# Flow_sensors.net
KiCad netlist of a schematic drawn in Altium Designer
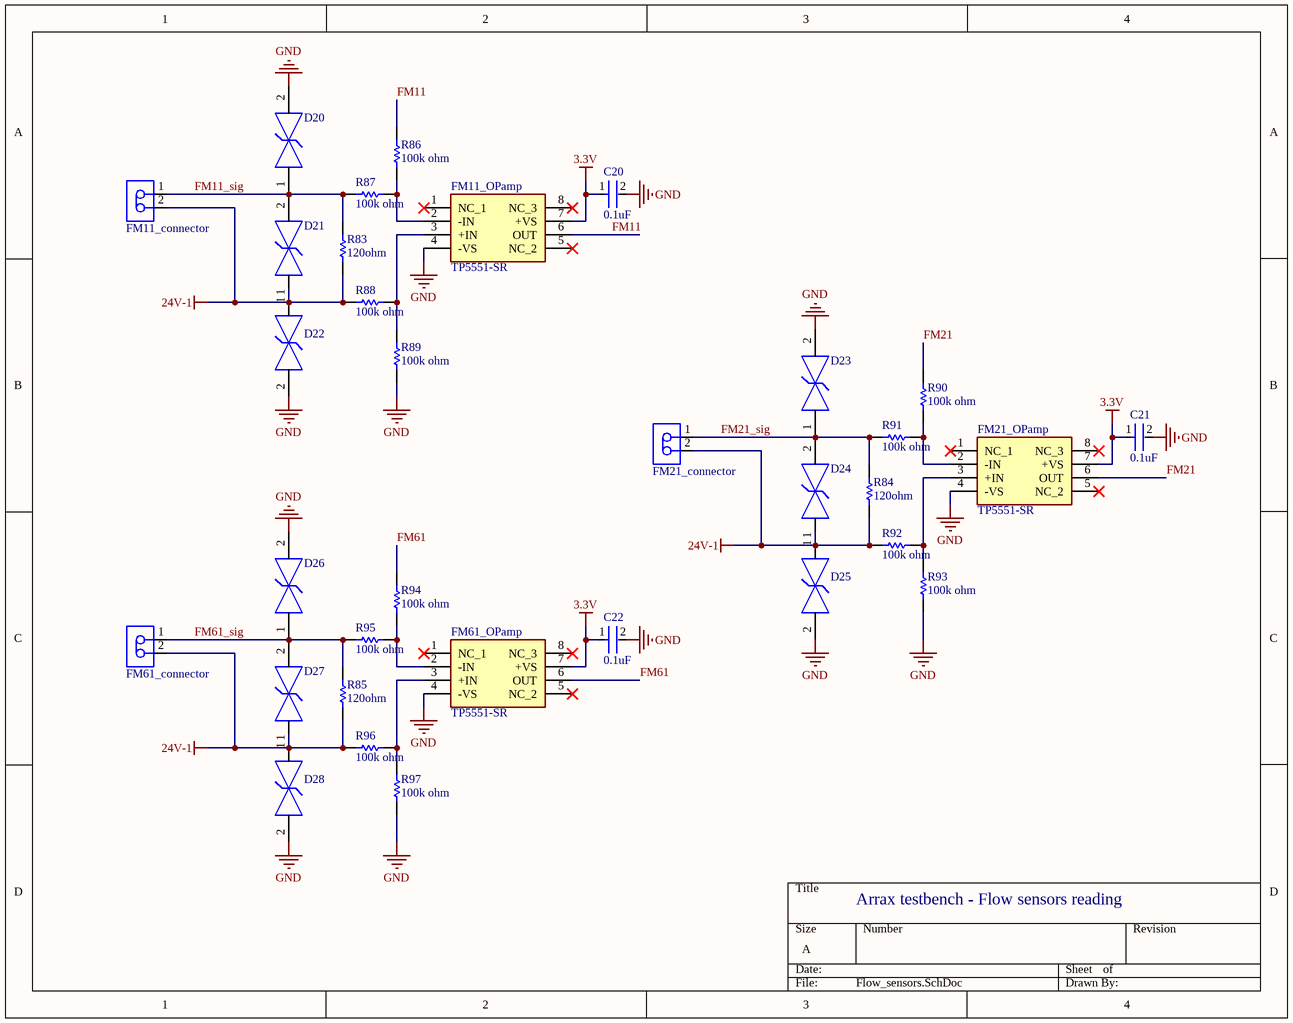
[diagram p0: Flow_sensors.SchDoc]

(export (version "E")
  (design (tool "Eeschema 10.0.6"))
  (components
    (comp (ref "C20")
      (value "0.1uF")
      (footprint "FP-CC0805-0_85-MFG")
      (description "CAP CER 0.1UF 50V X7R 0805")
      (fields (field (name "TOLERANCE") "0.1") (field (name "MANUFACTURER PART NUMBER") "CC0805KRX7R9BB104"))
      (libsource (lib "Altium Content Vault") (part "11868f565c42a9108669ba33697ecf6"))
    )
    (comp (ref "C21")
      (value "0.1uF")
      (footprint "FP-CC0805-0_85-MFG")
      (description "CAP CER 0.1UF 50V X7R 0805")
      (fields (field (name "TOLERANCE") "0.1") (field (name "MANUFACTURER PART NUMBER") "CC0805KRX7R9BB104"))
      (libsource (lib "Altium Content Vault") (part "11868f565c42a9108669ba33697ecf6"))
    )
    (comp (ref "C22")
      (value "0.1uF")
      (footprint "FP-CC0805-0_85-MFG")
      (description "CAP CER 0.1UF 50V X7R 0805")
      (fields (field (name "TOLERANCE") "0.1") (field (name "MANUFACTURER PART NUMBER") "CC0805KRX7R9BB104"))
      (libsource (lib "Altium Content Vault") (part "11868f565c42a9108669ba33697ecf6"))
    )
    (comp (ref "D20")
      (value "SMBJ33CA-13-F")
      (footprint "FP-SMB-CA-MFG")
      (description "TVS DIODE 33V 53.3V SMB")
      (libsource (lib "Altium Content Vault") (part "876f4347bf90aa6f500f43e3cd03972"))
    )
    (comp (ref "D21")
      (value "SMBJ33CA-13-F")
      (footprint "FP-SMB-CA-MFG")
      (description "TVS DIODE 33V 53.3V SMB")
      (libsource (lib "Altium Content Vault") (part "876f4347bf90aa6f500f43e3cd03972"))
    )
    (comp (ref "D22")
      (value "SMBJ33CA-13-F")
      (footprint "FP-SMB-CA-MFG")
      (description "TVS DIODE 33V 53.3V SMB")
      (libsource (lib "Altium Content Vault") (part "876f4347bf90aa6f500f43e3cd03972"))
    )
    (comp (ref "D23")
      (value "SMBJ33CA-13-F")
      (footprint "FP-SMB-CA-MFG")
      (description "TVS DIODE 33V 53.3V SMB")
      (libsource (lib "Altium Content Vault") (part "876f4347bf90aa6f500f43e3cd03972"))
    )
    (comp (ref "D24")
      (value "SMBJ33CA-13-F")
      (footprint "FP-SMB-CA-MFG")
      (description "TVS DIODE 33V 53.3V SMB")
      (libsource (lib "Altium Content Vault") (part "876f4347bf90aa6f500f43e3cd03972"))
    )
    (comp (ref "D25")
      (value "SMBJ33CA-13-F")
      (footprint "FP-SMB-CA-MFG")
      (description "TVS DIODE 33V 53.3V SMB")
      (libsource (lib "Altium Content Vault") (part "876f4347bf90aa6f500f43e3cd03972"))
    )
    (comp (ref "D26")
      (value "SMBJ33CA-13-F")
      (footprint "FP-SMB-CA-MFG")
      (description "TVS DIODE 33V 53.3V SMB")
      (libsource (lib "Altium Content Vault") (part "876f4347bf90aa6f500f43e3cd03972"))
    )
    (comp (ref "D27")
      (value "SMBJ33CA-13-F")
      (footprint "FP-SMB-CA-MFG")
      (description "TVS DIODE 33V 53.3V SMB")
      (libsource (lib "Altium Content Vault") (part "876f4347bf90aa6f500f43e3cd03972"))
    )
    (comp (ref "D28")
      (value "SMBJ33CA-13-F")
      (footprint "FP-SMB-CA-MFG")
      (description "TVS DIODE 33V 53.3V SMB")
      (libsource (lib "Altium Content Vault") (part "876f4347bf90aa6f500f43e3cd03972"))
    )
    (comp (ref "FM11_connector")
      (value "640456-2")
      (footprint "TECO-640456-2_V")
      (fields (field (name "MANUFACTURER") "TE Connectivity"))
      (libsource (lib "Altium Content Vault") (part "CN-2P-F-QF2"))
    )
    (comp (ref "FM11_OPamp")
      (value "TP5551-SR")
      (footprint "SamacSys:SOIC127P600X175-8N")
      (description "Integrated Circuit")
      (libsource (lib "*") (part "TP5551-SR"))
    )
    (comp (ref "FM21_connector")
      (value "640456-2")
      (footprint "TECO-640456-2_V")
      (fields (field (name "MANUFACTURER") "TE Connectivity"))
      (libsource (lib "Altium Content Vault") (part "CN-2P-F-QF2"))
    )
    (comp (ref "FM21_OPamp")
      (value "TP5551-SR")
      (footprint "SamacSys:SOIC127P600X175-8N")
      (description "Integrated Circuit")
      (libsource (lib "*") (part "TP5551-SR"))
    )
    (comp (ref "FM61_connector")
      (value "640456-2")
      (footprint "TECO-640456-2_V")
      (fields (field (name "MANUFACTURER") "TE Connectivity"))
      (libsource (lib "Altium Content Vault") (part "CN-2P-F-QF2"))
    )
    (comp (ref "FM61_OPamp")
      (value "TP5551-SR")
      (footprint "SamacSys:SOIC127P600X175-8N")
      (description "Integrated Circuit")
      (libsource (lib "*") (part "TP5551-SR"))
    )
    (comp (ref "R83")
      (value "120ohm")
      (footprint "RESC2013X60X40ML20T25")
      (fields (field (name "MANUFACTURER") "Panasonic") (field (name "PART NUMBER") "ERA6AEB121V"))
      (libsource (lib "Altium Content Vault") (part "RES"))
    )
    (comp (ref "R84")
      (value "120ohm")
      (footprint "RESC2013X60X40ML20T25")
      (fields (field (name "MANUFACTURER") "Panasonic") (field (name "PART NUMBER") "ERA6AEB121V"))
      (libsource (lib "Altium Content Vault") (part "RES"))
    )
    (comp (ref "R85")
      (value "120ohm")
      (footprint "RESC2013X60X40ML20T25")
      (fields (field (name "MANUFACTURER") "Panasonic") (field (name "PART NUMBER") "ERA6AEB121V"))
      (libsource (lib "Altium Content Vault") (part "RES"))
    )
    (comp (ref "R86")
      (value "100k ohm")
      (footprint "RESC2013X70X40ML20T20")
      (fields (field (name "PART NUMBER") "ERJ-6ENF1003V") (field (name "MANUFACTURER") "Panasonic"))
      (libsource (lib "Altium Content Vault") (part "RES"))
    )
    (comp (ref "R87")
      (value "100k ohm")
      (footprint "RESC2013X70X40ML20T20")
      (fields (field (name "PART NUMBER") "ERJ-6ENF1003V") (field (name "MANUFACTURER") "Panasonic"))
      (libsource (lib "Altium Content Vault") (part "RES"))
    )
    (comp (ref "R88")
      (value "100k ohm")
      (footprint "RESC2013X70X40ML20T20")
      (fields (field (name "PART NUMBER") "ERJ-6ENF1003V") (field (name "MANUFACTURER") "Panasonic"))
      (libsource (lib "Altium Content Vault") (part "RES"))
    )
    (comp (ref "R89")
      (value "100k ohm")
      (footprint "RESC2013X70X40ML20T20")
      (fields (field (name "PART NUMBER") "ERJ-6ENF1003V") (field (name "MANUFACTURER") "Panasonic"))
      (libsource (lib "Altium Content Vault") (part "RES"))
    )
    (comp (ref "R90")
      (value "100k ohm")
      (footprint "RESC2013X70X40ML20T20")
      (fields (field (name "PART NUMBER") "ERJ-6ENF1003V") (field (name "MANUFACTURER") "Panasonic"))
      (libsource (lib "Altium Content Vault") (part "RES"))
    )
    (comp (ref "R91")
      (value "100k ohm")
      (footprint "RESC2013X70X40ML20T20")
      (fields (field (name "PART NUMBER") "ERJ-6ENF1003V") (field (name "MANUFACTURER") "Panasonic"))
      (libsource (lib "Altium Content Vault") (part "RES"))
    )
    (comp (ref "R92")
      (value "100k ohm")
      (footprint "RESC2013X70X40ML20T20")
      (fields (field (name "PART NUMBER") "ERJ-6ENF1003V") (field (name "MANUFACTURER") "Panasonic"))
      (libsource (lib "Altium Content Vault") (part "RES"))
    )
    (comp (ref "R93")
      (value "100k ohm")
      (footprint "RESC2013X70X40ML20T20")
      (fields (field (name "PART NUMBER") "ERJ-6ENF1003V") (field (name "MANUFACTURER") "Panasonic"))
      (libsource (lib "Altium Content Vault") (part "RES"))
    )
    (comp (ref "R94")
      (value "100k ohm")
      (footprint "RESC2013X70X40ML20T20")
      (fields (field (name "PART NUMBER") "ERJ-6ENF1003V") (field (name "MANUFACTURER") "Panasonic"))
      (libsource (lib "Altium Content Vault") (part "RES"))
    )
    (comp (ref "R95")
      (value "100k ohm")
      (footprint "RESC2013X70X40ML20T20")
      (fields (field (name "PART NUMBER") "ERJ-6ENF1003V") (field (name "MANUFACTURER") "Panasonic"))
      (libsource (lib "Altium Content Vault") (part "RES"))
    )
    (comp (ref "R96")
      (value "100k ohm")
      (footprint "RESC2013X70X40ML20T20")
      (fields (field (name "PART NUMBER") "ERJ-6ENF1003V") (field (name "MANUFACTURER") "Panasonic"))
      (libsource (lib "Altium Content Vault") (part "RES"))
    )
    (comp (ref "R97")
      (value "100k ohm")
      (footprint "RESC2013X70X40ML20T20")
      (fields (field (name "PART NUMBER") "ERJ-6ENF1003V") (field (name "MANUFACTURER") "Panasonic"))
      (libsource (lib "Altium Content Vault") (part "RES"))
    )
  )
  (nets
    (net (code "1") (name "/FM11") (class "Default")
      (node (ref "FM11_OPamp") (pin "6") (pinfunction "OUT_6") (pintype "passive"))
      (node (ref "R86") (pin "2") (pinfunction "2_2") (pintype "passive"))
    )
    (net (code "2") (name "/FM11_sig") (class "Default")
      (node (ref "D20") (pin "1") (pinfunction "1_1") (pintype "passive"))
      (node (ref "D21") (pin "2") (pinfunction "2_2") (pintype "passive"))
      (node (ref "FM11_connector") (pin "1") (pinfunction "1_1") (pintype "passive"))
      (node (ref "R83") (pin "2") (pinfunction "2_2") (pintype "passive"))
      (node (ref "R87") (pin "2") (pinfunction "2_2") (pintype "passive"))
    )
    (net (code "3") (name "/FM21") (class "Default")
      (node (ref "FM21_OPamp") (pin "6") (pinfunction "OUT_6") (pintype "passive"))
      (node (ref "R90") (pin "2") (pinfunction "2_2") (pintype "passive"))
    )
    (net (code "4") (name "/FM21_sig") (class "Default")
      (node (ref "D23") (pin "1") (pinfunction "1_1") (pintype "passive"))
      (node (ref "D24") (pin "2") (pinfunction "2_2") (pintype "passive"))
      (node (ref "FM21_connector") (pin "1") (pinfunction "1_1") (pintype "passive"))
      (node (ref "R84") (pin "2") (pinfunction "2_2") (pintype "passive"))
      (node (ref "R91") (pin "2") (pinfunction "2_2") (pintype "passive"))
    )
    (net (code "5") (name "/FM61") (class "Default")
      (node (ref "FM61_OPamp") (pin "6") (pinfunction "OUT_6") (pintype "passive"))
      (node (ref "R94") (pin "2") (pinfunction "2_2") (pintype "passive"))
    )
    (net (code "6") (name "/FM61_sig") (class "Default")
      (node (ref "D26") (pin "1") (pinfunction "1_1") (pintype "passive"))
      (node (ref "D27") (pin "2") (pinfunction "2_2") (pintype "passive"))
      (node (ref "FM61_connector") (pin "1") (pinfunction "1_1") (pintype "passive"))
      (node (ref "R85") (pin "2") (pinfunction "2_2") (pintype "passive"))
      (node (ref "R95") (pin "1") (pinfunction "1_1") (pintype "passive"))
    )
    (net (code "7") (name "3.3V") (class "Default")
      (node (ref "C20") (pin "1") (pinfunction "1_1") (pintype "passive"))
      (node (ref "C21") (pin "1") (pinfunction "1_1") (pintype "passive"))
      (node (ref "C22") (pin "1") (pinfunction "1_1") (pintype "passive"))
      (node (ref "FM11_OPamp") (pin "7") (pinfunction "+VS_7") (pintype "passive"))
      (node (ref "FM21_OPamp") (pin "7") (pinfunction "+VS_7") (pintype "passive"))
      (node (ref "FM61_OPamp") (pin "7") (pinfunction "+VS_7") (pintype "passive"))
    )
    (net (code "8") (name "24V-1") (class "Default")
      (node (ref "D21") (pin "1") (pinfunction "1_1") (pintype "passive"))
      (node (ref "D22") (pin "1") (pinfunction "1_1") (pintype "passive"))
      (node (ref "D24") (pin "1") (pinfunction "1_1") (pintype "passive"))
      (node (ref "D25") (pin "1") (pinfunction "1_1") (pintype "passive"))
      (node (ref "D27") (pin "1") (pinfunction "1_1") (pintype "passive"))
      (node (ref "D28") (pin "1") (pinfunction "1_1") (pintype "passive"))
      (node (ref "FM11_connector") (pin "2") (pinfunction "2_2") (pintype "passive"))
      (node (ref "FM21_connector") (pin "2") (pinfunction "2_2") (pintype "passive"))
      (node (ref "FM61_connector") (pin "2") (pinfunction "2_2") (pintype "passive"))
      (node (ref "R83") (pin "1") (pinfunction "1_1") (pintype "passive"))
      (node (ref "R84") (pin "1") (pinfunction "1_1") (pintype "passive"))
      (node (ref "R85") (pin "1") (pinfunction "1_1") (pintype "passive"))
      (node (ref "R88") (pin "2") (pinfunction "2_2") (pintype "passive"))
      (node (ref "R92") (pin "2") (pinfunction "2_2") (pintype "passive"))
      (node (ref "R96") (pin "1") (pinfunction "1_1") (pintype "passive"))
    )
    (net (code "9") (name "GND") (class "Default")
      (node (ref "C20") (pin "2") (pinfunction "2_2") (pintype "passive"))
      (node (ref "C21") (pin "2") (pinfunction "2_2") (pintype "passive"))
      (node (ref "C22") (pin "2") (pinfunction "2_2") (pintype "passive"))
      (node (ref "D20") (pin "2") (pinfunction "2_2") (pintype "passive"))
      (node (ref "D22") (pin "2") (pinfunction "2_2") (pintype "passive"))
      (node (ref "D23") (pin "2") (pinfunction "2_2") (pintype "passive"))
      (node (ref "D25") (pin "2") (pinfunction "2_2") (pintype "passive"))
      (node (ref "D26") (pin "2") (pinfunction "2_2") (pintype "passive"))
      (node (ref "D28") (pin "2") (pinfunction "2_2") (pintype "passive"))
      (node (ref "FM11_OPamp") (pin "4") (pinfunction "-VS_4") (pintype "passive"))
      (node (ref "FM21_OPamp") (pin "4") (pinfunction "-VS_4") (pintype "passive"))
      (node (ref "FM61_OPamp") (pin "4") (pinfunction "-VS_4") (pintype "passive"))
      (node (ref "R89") (pin "1") (pinfunction "1_1") (pintype "passive"))
      (node (ref "R93") (pin "1") (pinfunction "1_1") (pintype "passive"))
      (node (ref "R97") (pin "1") (pinfunction "1_1") (pintype "passive"))
    )
    (net (code "10") (name "Net-(FM11_OPamp-+IN)") (class "Default")
      (node (ref "FM11_OPamp") (pin "3") (pinfunction "+IN_3") (pintype "passive"))
      (node (ref "R88") (pin "1") (pinfunction "1_1") (pintype "passive"))
      (node (ref "R89") (pin "2") (pinfunction "2_2") (pintype "passive"))
    )
    (net (code "11") (name "Net-(FM11_OPamp--IN)") (class "Default")
      (node (ref "FM11_OPamp") (pin "2") (pinfunction "-IN_2") (pintype "passive"))
      (node (ref "R86") (pin "1") (pinfunction "1_1") (pintype "passive"))
      (node (ref "R87") (pin "1") (pinfunction "1_1") (pintype "passive"))
    )
    (net (code "12") (name "Net-(FM21_OPamp-+IN)") (class "Default")
      (node (ref "FM21_OPamp") (pin "3") (pinfunction "+IN_3") (pintype "passive"))
      (node (ref "R92") (pin "1") (pinfunction "1_1") (pintype "passive"))
      (node (ref "R93") (pin "2") (pinfunction "2_2") (pintype "passive"))
    )
    (net (code "13") (name "Net-(FM21_OPamp--IN)") (class "Default")
      (node (ref "FM21_OPamp") (pin "2") (pinfunction "-IN_2") (pintype "passive"))
      (node (ref "R90") (pin "1") (pinfunction "1_1") (pintype "passive"))
      (node (ref "R91") (pin "1") (pinfunction "1_1") (pintype "passive"))
    )
    (net (code "14") (name "Net-(FM61_OPamp-+IN)") (class "Default")
      (node (ref "FM61_OPamp") (pin "3") (pinfunction "+IN_3") (pintype "passive"))
      (node (ref "R96") (pin "2") (pinfunction "2_2") (pintype "passive"))
      (node (ref "R97") (pin "2") (pinfunction "2_2") (pintype "passive"))
    )
    (net (code "15") (name "Net-(FM61_OPamp--IN)") (class "Default")
      (node (ref "FM61_OPamp") (pin "2") (pinfunction "-IN_2") (pintype "passive"))
      (node (ref "R94") (pin "1") (pinfunction "1_1") (pintype "passive"))
      (node (ref "R95") (pin "2") (pinfunction "2_2") (pintype "passive"))
    )
    (net (code "16") (name "unconnected-(FM11_OPamp-NC_1-Pad1)") (class "Default")
      (node (ref "FM11_OPamp") (pin "1") (pinfunction "NC_1_1") (pintype "passive+no_connect"))
    )
    (net (code "17") (name "unconnected-(FM11_OPamp-NC_2-Pad5)") (class "Default")
      (node (ref "FM11_OPamp") (pin "5") (pinfunction "NC_2_5") (pintype "passive+no_connect"))
    )
    (net (code "18") (name "unconnected-(FM11_OPamp-NC_3-Pad8)") (class "Default")
      (node (ref "FM11_OPamp") (pin "8") (pinfunction "NC_3_8") (pintype "passive+no_connect"))
    )
    (net (code "19") (name "unconnected-(FM21_OPamp-NC_1-Pad1)") (class "Default")
      (node (ref "FM21_OPamp") (pin "1") (pinfunction "NC_1_1") (pintype "passive+no_connect"))
    )
    (net (code "20") (name "unconnected-(FM21_OPamp-NC_2-Pad5)") (class "Default")
      (node (ref "FM21_OPamp") (pin "5") (pinfunction "NC_2_5") (pintype "passive+no_connect"))
    )
    (net (code "21") (name "unconnected-(FM21_OPamp-NC_3-Pad8)") (class "Default")
      (node (ref "FM21_OPamp") (pin "8") (pinfunction "NC_3_8") (pintype "passive+no_connect"))
    )
    (net (code "22") (name "unconnected-(FM61_OPamp-NC_1-Pad1)") (class "Default")
      (node (ref "FM61_OPamp") (pin "1") (pinfunction "NC_1_1") (pintype "passive+no_connect"))
    )
    (net (code "23") (name "unconnected-(FM61_OPamp-NC_2-Pad5)") (class "Default")
      (node (ref "FM61_OPamp") (pin "5") (pinfunction "NC_2_5") (pintype "passive+no_connect"))
    )
    (net (code "24") (name "unconnected-(FM61_OPamp-NC_3-Pad8)") (class "Default")
      (node (ref "FM61_OPamp") (pin "8") (pinfunction "NC_3_8") (pintype "passive+no_connect"))
    )
  )
)
